# MB_downlink_phy.net
KiCad netlist of a schematic drawn in Altium Designer
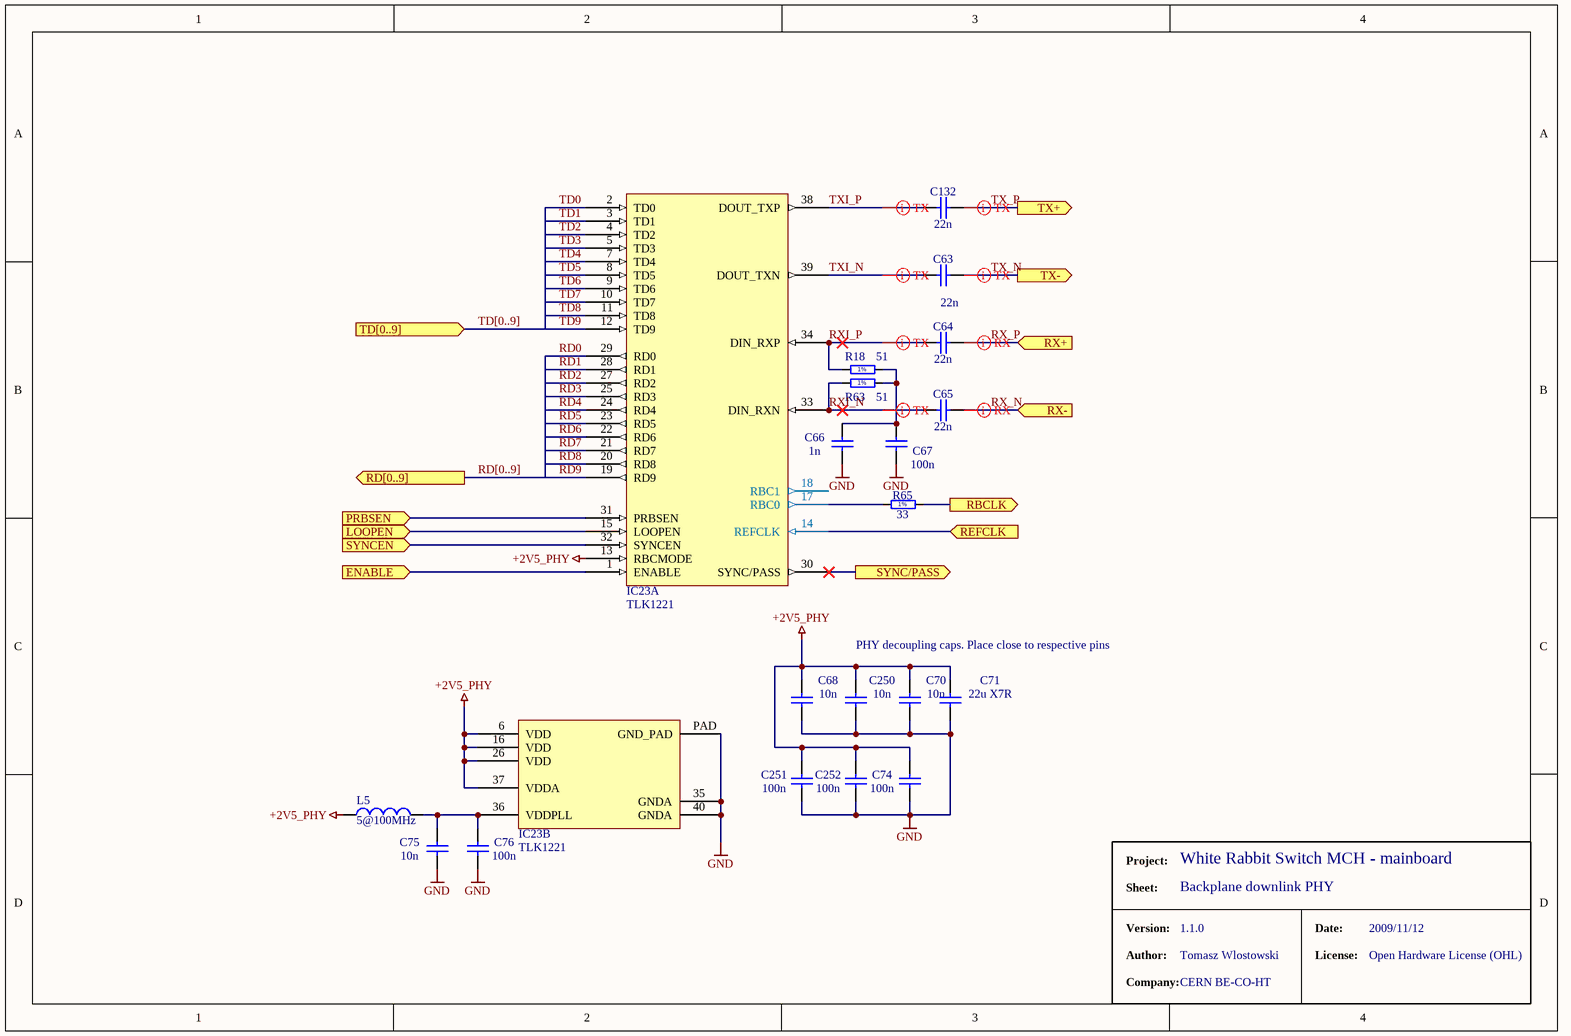
[diagram p0: MB_downlink_phy.SchDoc]

(export (version "E")
  (design (tool "Eeschema 10.0.6"))
  (components
    (comp (ref "C63")
      (value "22n")
      (footprint "CAPC1005X55N")
      (description "Non-polarised capacitor")
      (fields
        (field (name "PART NUMBER") "CC0402_22NF_16V_10%_X7R")
        (field (name "VOLTAGE") "16V")
        (field (name "AUTHOR") "CERN DEM JLC")
      )
      (libsource (lib "Capacitors") (part "Capacitor - non polarized"))
    )
    (comp (ref "C64")
      (value "22n")
      (footprint "CAPC1005X55N")
      (description "Non-polarised capacitor")
      (fields
        (field (name "PART NUMBER") "CC0402_22NF_16V_10%_X7R")
        (field (name "VOLTAGE") "16V")
        (field (name "AUTHOR") "CERN DEM JLC")
      )
      (libsource (lib "Capacitors") (part "Capacitor - non polarized"))
    )
    (comp (ref "C65")
      (value "22n")
      (footprint "CAPC1005X55N")
      (description "Non-polarised capacitor")
      (fields
        (field (name "PART NUMBER") "CC0402_22NF_16V_10%_X7R")
        (field (name "VOLTAGE") "16V")
        (field (name "AUTHOR") "CERN DEM JLC")
      )
      (libsource (lib "Capacitors") (part "Capacitor - non polarized"))
    )
    (comp (ref "C66")
      (value "1n")
      (footprint "CAPC1005X55N")
      (description "Non-polarised capacitor")
      (fields
        (field (name "PART NUMBER") "CC0402_1.0NF_50V_10%_X7R")
        (field (name "VOLTAGE") "50V")
        (field (name "AUTHOR") "CERN DEM JLC")
      )
      (libsource (lib "Capacitors") (part "Capacitor - non polarized"))
    )
    (comp (ref "C67")
      (value "100n")
      (footprint "CAPC1005X55N")
      (description "Non-polarised capacitor")
      (fields
        (field (name "PART NUMBER") "CC0402_100NF_16V_10%_X7R")
        (field (name "VOLTAGE") "16V")
        (field (name "AUTHOR") "CERN DEM JLC")
      )
      (libsource (lib "Capacitors") (part "Capacitor - non polarized"))
    )
    (comp (ref "C68")
      (value "10n")
      (footprint "CAPC1005X55N")
      (description "Non-polarised capacitor")
      (fields
        (field (name "PART NUMBER") "CC0402_10NF_16V_10%_X7R")
        (field (name "VOLTAGE") "16V")
        (field (name "AUTHOR") "CERN DEM JLC")
      )
      (libsource (lib "Capacitors") (part "Capacitor - non polarized"))
    )
    (comp (ref "C70")
      (value "10n")
      (footprint "CAPC1005X55N")
      (description "Non-polarised capacitor")
      (fields
        (field (name "PART NUMBER") "CC0402_10NF_16V_10%_X7R")
        (field (name "VOLTAGE") "16V")
        (field (name "AUTHOR") "CERN DEM JLC")
      )
      (libsource (lib "Capacitors") (part "Capacitor - non polarized"))
    )
    (comp (ref "C71")
      (value "22u X7R")
      (footprint "CAPC2012X135N")
      (description "Non-polarised capacitor")
      (fields
        (field (name "PART NUMBER") "CC0805_22uF_6.3V_20%_X5R")
        (field (name "VOLTAGE") "6.3V")
        (field (name "AUTHOR") "CERN DEM JLC")
      )
      (libsource (lib "Capacitors") (part "Capacitor - non polarized"))
    )
    (comp (ref "C74")
      (value "100n")
      (footprint "CAPC1005X55N")
      (description "Non-polarised capacitor")
      (fields
        (field (name "PART NUMBER") "CC0402_100NF_16V_10%_X7R")
        (field (name "VOLTAGE") "16V")
        (field (name "AUTHOR") "CERN DEM JLC")
      )
      (libsource (lib "Capacitors") (part "Capacitor - non polarized"))
    )
    (comp (ref "C75")
      (value "10n")
      (footprint "CAPC1005X55N")
      (description "Non-polarised capacitor")
      (fields
        (field (name "PART NUMBER") "CC0402_10NF_16V_10%_X7R")
        (field (name "VOLTAGE") "16V")
        (field (name "AUTHOR") "CERN DEM JLC")
      )
      (libsource (lib "Capacitors") (part "Capacitor - non polarized"))
    )
    (comp (ref "C76")
      (value "100n")
      (footprint "CAPC1005X55N")
      (description "Non-polarised capacitor")
      (fields
        (field (name "PART NUMBER") "CC0402_100NF_16V_10%_X7R")
        (field (name "VOLTAGE") "16V")
        (field (name "AUTHOR") "CERN DEM JLC")
      )
      (libsource (lib "Capacitors") (part "Capacitor - non polarized"))
    )
    (comp (ref "C132")
      (value "22n")
      (footprint "CAPC1005X55N")
      (description "Non-polarised capacitor")
      (fields
        (field (name "PART NUMBER") "CC0402_22NF_16V_10%_X7R")
        (field (name "VOLTAGE") "16V")
        (field (name "AUTHOR") "CERN DEM JLC")
      )
      (libsource (lib "Capacitors") (part "Capacitor - non polarized"))
    )
    (comp (ref "C250")
      (value "10n")
      (footprint "CAPC1005X55N")
      (description "Non-polarised capacitor")
      (fields
        (field (name "PART NUMBER") "CC0402_10NF_16V_10%_X7R")
        (field (name "VOLTAGE") "16V")
        (field (name "AUTHOR") "CERN DEM JLC")
      )
      (libsource (lib "Capacitors") (part "Capacitor - non polarized"))
    )
    (comp (ref "C251")
      (value "100n")
      (footprint "CAPC1005X55N")
      (description "Non-polarised capacitor")
      (fields
        (field (name "PART NUMBER") "CC0402_100NF_16V_10%_X7R")
        (field (name "VOLTAGE") "16V")
        (field (name "AUTHOR") "CERN DEM JLC")
      )
      (libsource (lib "Capacitors") (part "Capacitor - non polarized"))
    )
    (comp (ref "C252")
      (value "100n")
      (footprint "CAPC1005X55N")
      (description "Non-polarised capacitor")
      (fields
        (field (name "PART NUMBER") "CC0402_100NF_16V_10%_X7R")
        (field (name "VOLTAGE") "16V")
        (field (name "AUTHOR") "CERN DEM JLC")
      )
      (libsource (lib "Capacitors") (part "Capacitor - non polarized"))
    )
    (comp (ref "IC23")
      (value "TLK1221")
      (footprint "QFN40_powerpad")
      (description "Texas Instruments Gigabit Ethernet PHY with deterministic clocking and LVPECL output interface")
      (libsource (lib "wr_switch") (part "TLK1221"))
    )
    (comp (ref "L5")
      (value "5@100MHz")
      (footprint "INDC1608-0603")
      (description "Ferrite bead")
      (fields (field (name "Comment") "Inductor") (field (name "PUBLISHER") "Altium Limited"))
      (libsource (lib "Miscellaneous Devices") (part "Inductor"))
    )
    (comp (ref "R18")
      (value "51")
      (footprint "RESC1005X40N")
      (description "Resistor - 1%")
      (fields
        (field (name "PART NUMBER") "R0402_51R_1%_0.0625W_100PPM")
        (field (name "POWER") "0.0625W")
        (field (name "AUTHOR") "CERN DEM JLC")
      )
      (libsource (lib "Resistors") (part "Resistor - 1%"))
    )
    (comp (ref "R63")
      (value "51")
      (footprint "RESC1005X40N")
      (description "Resistor - 1%")
      (fields
        (field (name "PART NUMBER") "R0402_51R_1%_0.0625W_100PPM")
        (field (name "POWER") "0.0625W")
        (field (name "AUTHOR") "CERN DEM JLC")
      )
      (libsource (lib "Resistors") (part "Resistor - 1%"))
    )
    (comp (ref "R65")
      (value "33")
      (footprint "RESC1005X40N")
      (description "Resistor - 1%")
      (fields
        (field (name "PART NUMBER") "R0402_33R_1%_0.0625W_100PPM")
        (field (name "POWER") "0.0625W")
        (field (name "AUTHOR") "CERN DEM JLC")
      )
      (libsource (lib "Resistors") (part "Resistor - 1%"))
    )
  )
  (nets
    (net (code "1") (name "+2V5_PHY") (class "Default")
      (node (ref "C250") (pin "2") (pinfunction "2_2") (pintype "passive"))
      (node (ref "C251") (pin "2") (pinfunction "2_2") (pintype "passive"))
      (node (ref "C252") (pin "2") (pinfunction "2_2") (pintype "passive"))
      (node (ref "C68") (pin "2") (pinfunction "2_2") (pintype "passive"))
      (node (ref "C70") (pin "2") (pinfunction "2_2") (pintype "passive"))
      (node (ref "C71") (pin "2") (pinfunction "2_2") (pintype "passive"))
      (node (ref "C74") (pin "2") (pinfunction "2_2") (pintype "passive"))
      (node (ref "IC23") (pin "13") (pinfunction "RBCMODE_13") (pintype "input"))
      (node (ref "IC23") (pin "16") (pinfunction "VDD_16") (pintype "power_in"))
      (node (ref "IC23") (pin "26") (pinfunction "VDD_26") (pintype "power_in"))
      (node (ref "IC23") (pin "37") (pinfunction "VDDA_37") (pintype "power_in"))
      (node (ref "IC23") (pin "6") (pinfunction "VDD_6") (pintype "power_in"))
      (node (ref "L5") (pin "1") (pinfunction "1_1") (pintype "passive"))
    )
    (net (code "2") (name "/ENABLE") (class "Default")
      (node (ref "IC23") (pin "1") (pinfunction "ENABLE_1") (pintype "input"))
    )
    (net (code "3") (name "/LOOPEN") (class "Default")
      (node (ref "IC23") (pin "15") (pinfunction "LOOPEN_15") (pintype "input"))
    )
    (net (code "4") (name "/PRBSEN") (class "Default")
      (node (ref "IC23") (pin "31") (pinfunction "PRBSEN_31") (pintype "input"))
    )
    (net (code "5") (name "/RBCLK") (class "Default")
      (node (ref "R65") (pin "2") (pinfunction "2_2") (pintype "passive"))
    )
    (net (code "6") (name "/RD0") (class "Default")
      (node (ref "IC23") (pin "29") (pinfunction "RD0_29") (pintype "output"))
    )
    (net (code "7") (name "/RD1") (class "Default")
      (node (ref "IC23") (pin "28") (pinfunction "RD1_28") (pintype "output"))
    )
    (net (code "8") (name "/RD2") (class "Default")
      (node (ref "IC23") (pin "27") (pinfunction "RD2_27") (pintype "output"))
    )
    (net (code "9") (name "/RD3") (class "Default")
      (node (ref "IC23") (pin "25") (pinfunction "RD3_25") (pintype "output"))
    )
    (net (code "10") (name "/RD4") (class "Default")
      (node (ref "IC23") (pin "24") (pinfunction "RD4_24") (pintype "output"))
    )
    (net (code "11") (name "/RD5") (class "Default")
      (node (ref "IC23") (pin "23") (pinfunction "RD5_23") (pintype "output"))
    )
    (net (code "12") (name "/RD6") (class "Default")
      (node (ref "IC23") (pin "22") (pinfunction "RD6_22") (pintype "output"))
    )
    (net (code "13") (name "/RD7") (class "Default")
      (node (ref "IC23") (pin "21") (pinfunction "RD7_21") (pintype "output"))
    )
    (net (code "14") (name "/RD8") (class "Default")
      (node (ref "IC23") (pin "20") (pinfunction "RD8_20") (pintype "output"))
    )
    (net (code "15") (name "/RD9") (class "Default")
      (node (ref "IC23") (pin "19") (pinfunction "RD9_19") (pintype "output"))
    )
    (net (code "17") (name "/REFCLK") (class "Default")
      (node (ref "IC23") (pin "14") (pinfunction "REFCLK_14") (pintype "input"))
    )
    (net (code "18") (name "/RXI_N") (class "Default")
      (node (ref "C65") (pin "1") (pinfunction "1_1") (pintype "passive"))
      (node (ref "IC23") (pin "33") (pinfunction "DIN_RXN_33") (pintype "input"))
      (node (ref "R63") (pin "1") (pinfunction "1_1") (pintype "passive"))
    )
    (net (code "19") (name "/RXI_P") (class "Default")
      (node (ref "C64") (pin "1") (pinfunction "1_1") (pintype "passive"))
      (node (ref "IC23") (pin "34") (pinfunction "DIN_RXP_34") (pintype "input"))
      (node (ref "R18") (pin "1") (pinfunction "1_1") (pintype "passive"))
    )
    (net (code "20") (name "/RX_N") (class "Default")
      (node (ref "C65") (pin "2") (pinfunction "2_2") (pintype "passive"))
    )
    (net (code "21") (name "/RX_P") (class "Default")
      (node (ref "C64") (pin "2") (pinfunction "2_2") (pintype "passive"))
    )
    (net (code "22") (name "/SYNCEN") (class "Default")
      (node (ref "IC23") (pin "32") (pinfunction "SYNCEN_32") (pintype "input"))
    )
    (net (code "23") (name "/SYNC{slash}PASS") (class "Default")
      (node (ref "IC23") (pin "30") (pinfunction "SYNC/PASS_30") (pintype "output+no_connect"))
    )
    (net (code "24") (name "/TD0") (class "Default")
      (node (ref "IC23") (pin "2") (pinfunction "TD0_2") (pintype "input"))
    )
    (net (code "25") (name "/TD1") (class "Default")
      (node (ref "IC23") (pin "3") (pinfunction "TD1_3") (pintype "input"))
    )
    (net (code "26") (name "/TD2") (class "Default")
      (node (ref "IC23") (pin "4") (pinfunction "TD2_4") (pintype "input"))
    )
    (net (code "27") (name "/TD3") (class "Default")
      (node (ref "IC23") (pin "5") (pinfunction "TD3_5") (pintype "input"))
    )
    (net (code "28") (name "/TD4") (class "Default")
      (node (ref "IC23") (pin "7") (pinfunction "TD4_7") (pintype "input"))
    )
    (net (code "29") (name "/TD5") (class "Default")
      (node (ref "IC23") (pin "8") (pinfunction "TD5_8") (pintype "input"))
    )
    (net (code "30") (name "/TD6") (class "Default")
      (node (ref "IC23") (pin "9") (pinfunction "TD6_9") (pintype "input"))
    )
    (net (code "31") (name "/TD7") (class "Default")
      (node (ref "IC23") (pin "10") (pinfunction "TD7_10") (pintype "input"))
    )
    (net (code "32") (name "/TD8") (class "Default")
      (node (ref "IC23") (pin "11") (pinfunction "TD8_11") (pintype "input"))
    )
    (net (code "33") (name "/TD9") (class "Default")
      (node (ref "IC23") (pin "12") (pinfunction "TD9_12") (pintype "input"))
    )
    (net (code "35") (name "/TXI_N") (class "Default")
      (node (ref "C63") (pin "1") (pinfunction "1_1") (pintype "passive"))
      (node (ref "IC23") (pin "39") (pinfunction "DOUT_TXN_39") (pintype "output"))
    )
    (net (code "36") (name "/TXI_P") (class "Default")
      (node (ref "C132") (pin "1") (pinfunction "1_1") (pintype "passive"))
      (node (ref "IC23") (pin "38") (pinfunction "DOUT_TXP_38") (pintype "output"))
    )
    (net (code "37") (name "/TX_N") (class "Default")
      (node (ref "C63") (pin "2") (pinfunction "2_2") (pintype "passive"))
    )
    (net (code "38") (name "/TX_P") (class "Default")
      (node (ref "C132") (pin "2") (pinfunction "2_2") (pintype "passive"))
    )
    (net (code "39") (name "GND") (class "Default")
      (node (ref "C250") (pin "1") (pinfunction "1_1") (pintype "passive"))
      (node (ref "C251") (pin "1") (pinfunction "1_1") (pintype "passive"))
      (node (ref "C252") (pin "1") (pinfunction "1_1") (pintype "passive"))
      (node (ref "C66") (pin "1") (pinfunction "1_1") (pintype "passive"))
      (node (ref "C67") (pin "1") (pinfunction "1_1") (pintype "passive"))
      (node (ref "C68") (pin "1") (pinfunction "1_1") (pintype "passive"))
      (node (ref "C70") (pin "1") (pinfunction "1_1") (pintype "passive"))
      (node (ref "C71") (pin "1") (pinfunction "1_1") (pintype "passive"))
      (node (ref "C74") (pin "1") (pinfunction "1_1") (pintype "passive"))
      (node (ref "C75") (pin "1") (pinfunction "1_1") (pintype "passive"))
      (node (ref "C76") (pin "1") (pinfunction "1_1") (pintype "passive"))
      (node (ref "IC23") (pin "35") (pinfunction "GNDA_35") (pintype "power_in"))
      (node (ref "IC23") (pin "40") (pinfunction "GNDA_40") (pintype "power_in"))
      (node (ref "IC23") (pin "PAD") (pinfunction "GND_PAD_PAD") (pintype "power_in"))
    )
    (net (code "40") (name "Net-(C66-Pad2)") (class "Default")
      (node (ref "C66") (pin "2") (pinfunction "2_2") (pintype "passive"))
      (node (ref "C67") (pin "2") (pinfunction "2_2") (pintype "passive"))
      (node (ref "R18") (pin "2") (pinfunction "2_2") (pintype "passive"))
      (node (ref "R63") (pin "2") (pinfunction "2_2") (pintype "passive"))
    )
    (net (code "41") (name "Net-(IC23A-RBC0)") (class "Default")
      (node (ref "IC23") (pin "17") (pinfunction "RBC0_17") (pintype "output"))
      (node (ref "R65") (pin "1") (pinfunction "1_1") (pintype "passive"))
    )
    (net (code "42") (name "Net-(IC23B-VDDPLL)") (class "Default")
      (node (ref "C75") (pin "2") (pinfunction "2_2") (pintype "passive"))
      (node (ref "C76") (pin "2") (pinfunction "2_2") (pintype "passive"))
      (node (ref "IC23") (pin "36") (pinfunction "VDDPLL_36") (pintype "power_in"))
      (node (ref "L5") (pin "2") (pinfunction "2_2") (pintype "passive"))
    )
    (net (code "43") (name "unconnected-(IC23A-RBC1-Pad18)") (class "Default")
      (node (ref "IC23") (pin "18") (pinfunction "RBC1_18") (pintype "output"))
    )
  )
)
